# Driver_Low.net
KiCad netlist of a schematic drawn in EAGLE
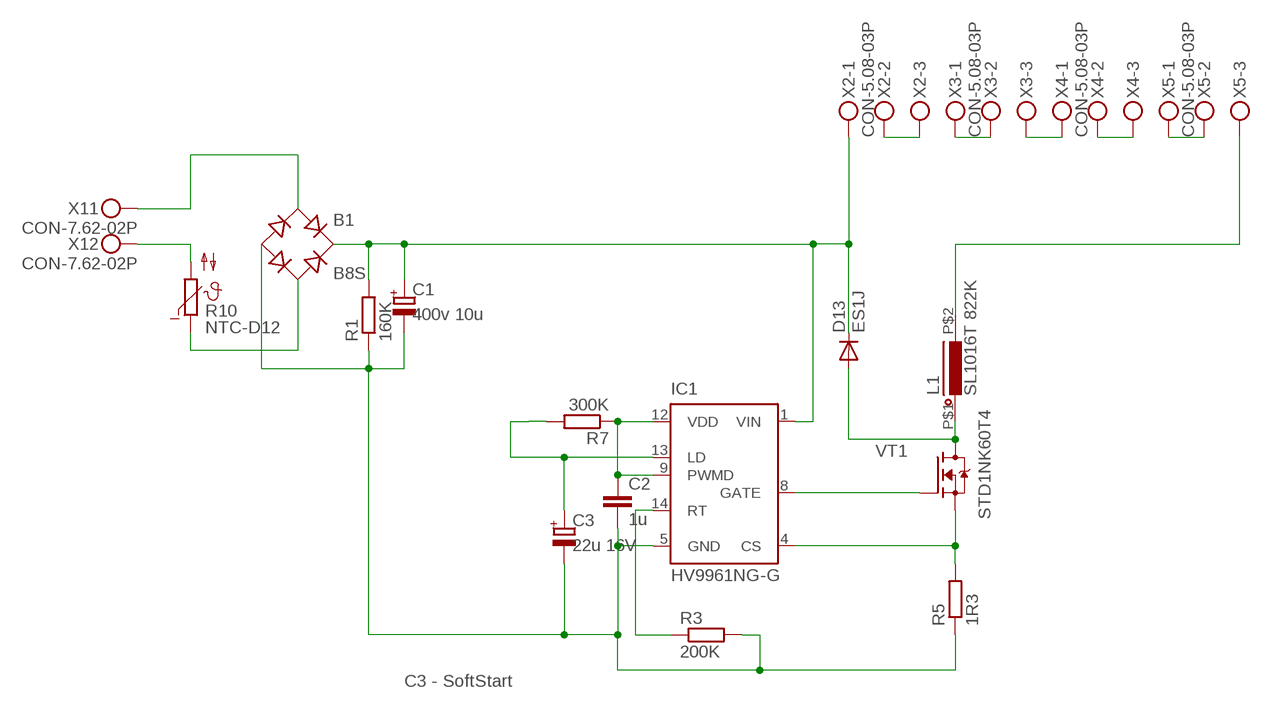
[diagram p0: schematic, sheet 1]
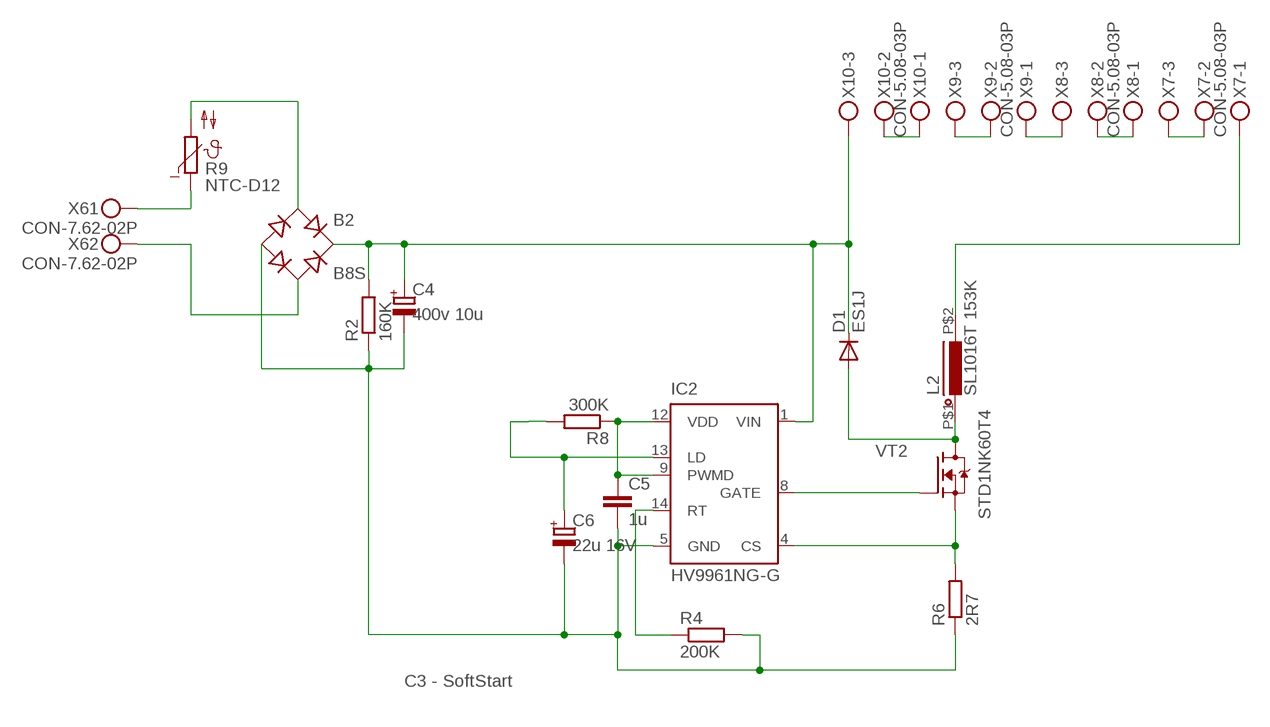
[diagram p1: schematic, sheet 2]

(export (version "E")
  (design (tool "Eeschema 10.0.6"))
  (components
    (comp (ref "B2")
      (value "B8S")
      (footprint "eagle-import:MBS")
      (libsource (lib "eagle-import") (part "BS6"))
    )
    (comp (ref "C4")
      (value "400v 10u")
      (footprint "eagle-import:E3,5-8")
      (libsource (lib "eagle-import") (part "CAP-POL_E3.5-8"))
    )
    (comp (ref "C5")
      (value "1u")
      (footprint "eagle-import:C0805")
      (libsource (lib "eagle-import") (part "CAP_0805"))
    )
    (comp (ref "C6")
      (value "22u 16V")
      (footprint "eagle-import:CT3528")
      (libsource (lib "eagle-import") (part "CAP-POL_3528"))
    )
    (comp (ref "D1")
      (value "ES1J")
      (footprint "eagle-import:DO214AC")
      (libsource (lib "eagle-import") (part "DIODE_ES1J"))
    )
    (comp (ref "IC2")
      (value "HV9961NG-G")
      (footprint "eagle-import:SOIC-16NG")
      (libsource (lib "eagle-import") (part "HV9910BNG"))
    )
    (comp (ref "L2")
      (value "SL1016T 153K")
      (footprint "eagle-import:SL1016")
      (libsource (lib "eagle-import") (part "INDUCTORSL1016"))
    )
    (comp (ref "R2")
      (value "160K")
      (footprint "eagle-import:MF-0125")
      (libsource (lib "eagle-import") (part "R_MF-0125"))
    )
    (comp (ref "R4")
      (value "200K")
      (footprint "eagle-import:R0805")
      (libsource (lib "eagle-import") (part "R_0805"))
    )
    (comp (ref "R6")
      (value "2R7")
      (footprint "eagle-import:R0805")
      (libsource (lib "eagle-import") (part "R_0805"))
    )
    (comp (ref "R8")
      (value "300K")
      (footprint "eagle-import:R0805")
      (libsource (lib "eagle-import") (part "R_0805"))
    )
    (comp (ref "R9")
      (value "NTC-D12")
      (footprint "eagle-import:NTC-D12")
      (libsource (lib "eagle-import") (part "NTC-D12"))
    )
    (comp (ref "VT2")
      (value "STD1NK60T4")
      (footprint "eagle-import:DPAK")
      (libsource (lib "eagle-import") (part "FET-NDPAK"))
    )
    (comp (ref "X6")
      (value "CON-7.62-02P")
      (footprint "eagle-import:KF25C-7.62-02P-13")
      (libsource (lib "eagle-import") (part "CON-7.62-02P"))
    )
    (comp (ref "X7")
      (value "CON-5.08-03P")
      (footprint "eagle-import:MKDSN1,5_3-5,08")
      (libsource (lib "eagle-import") (part "CON-5.08-03P"))
    )
    (comp (ref "X8")
      (value "CON-5.08-03P")
      (footprint "eagle-import:MKDSN1,5_3-5,08")
      (libsource (lib "eagle-import") (part "CON-5.08-03P"))
    )
    (comp (ref "X9")
      (value "CON-5.08-03P")
      (footprint "eagle-import:MKDSN1,5_3-5,08")
      (libsource (lib "eagle-import") (part "CON-5.08-03P"))
    )
    (comp (ref "X10")
      (value "CON-5.08-03P")
      (footprint "eagle-import:MKDSN1,5_3-5,08")
      (libsource (lib "eagle-import") (part "CON-5.08-03P"))
    )
    (comp (ref "B1")
      (value "B8S")
      (footprint "eagle-import:MBS")
      (libsource (lib "eagle-import") (part "BS6"))
    )
    (comp (ref "C1")
      (value "400v 10u")
      (footprint "eagle-import:E3,5-8")
      (libsource (lib "eagle-import") (part "CAP-POL_E3.5-8"))
    )
    (comp (ref "C2")
      (value "1u")
      (footprint "eagle-import:C0805")
      (libsource (lib "eagle-import") (part "CAP_0805"))
    )
    (comp (ref "C3")
      (value "22u 16V")
      (footprint "eagle-import:CT3528")
      (libsource (lib "eagle-import") (part "CAP-POL_3528"))
    )
    (comp (ref "D13")
      (value "ES1J")
      (footprint "eagle-import:DO214AC")
      (libsource (lib "eagle-import") (part "DIODE_ES1J"))
    )
    (comp (ref "IC1")
      (value "HV9961NG-G")
      (footprint "eagle-import:SOIC-16NG")
      (libsource (lib "eagle-import") (part "HV9910BNG"))
    )
    (comp (ref "L1")
      (value "SL1016T 822K")
      (footprint "eagle-import:SL1016")
      (libsource (lib "eagle-import") (part "INDUCTORSL1016"))
    )
    (comp (ref "R1")
      (value "160K")
      (footprint "eagle-import:MF-0125")
      (libsource (lib "eagle-import") (part "R_MF-0125"))
    )
    (comp (ref "R3")
      (value "200K")
      (footprint "eagle-import:R0805")
      (libsource (lib "eagle-import") (part "R_0805"))
    )
    (comp (ref "R5")
      (value "1R3")
      (footprint "eagle-import:R0805")
      (libsource (lib "eagle-import") (part "R_0805"))
    )
    (comp (ref "R7")
      (value "300K")
      (footprint "eagle-import:R0805")
      (libsource (lib "eagle-import") (part "R_0805"))
    )
    (comp (ref "R10")
      (value "NTC-D12")
      (footprint "eagle-import:NTC-D12")
      (libsource (lib "eagle-import") (part "NTC-D12"))
    )
    (comp (ref "VT1")
      (value "STD1NK60T4")
      (footprint "eagle-import:DPAK")
      (libsource (lib "eagle-import") (part "FET-NDPAK"))
    )
    (comp (ref "X1")
      (value "CON-7.62-02P")
      (footprint "eagle-import:KF25C-7.62-02P-13")
      (libsource (lib "eagle-import") (part "CON-7.62-02P"))
    )
    (comp (ref "X2")
      (value "CON-5.08-03P")
      (footprint "eagle-import:MKDSN1,5_3-5,08")
      (libsource (lib "eagle-import") (part "CON-5.08-03P"))
    )
    (comp (ref "X3")
      (value "CON-5.08-03P")
      (footprint "eagle-import:MKDSN1,5_3-5,08")
      (libsource (lib "eagle-import") (part "CON-5.08-03P"))
    )
    (comp (ref "X4")
      (value "CON-5.08-03P")
      (footprint "eagle-import:MKDSN1,5_3-5,08")
      (libsource (lib "eagle-import") (part "CON-5.08-03P"))
    )
    (comp (ref "X5")
      (value "CON-5.08-03P")
      (footprint "eagle-import:MKDSN1,5_3-5,08")
      (libsource (lib "eagle-import") (part "CON-5.08-03P"))
    )
  )
  (nets
    (net (code "1") (name "Net-(B1-PadAC2)") (class "Default")
      (node (ref "B1") (pin "AC2") (pinfunction "AC2_AC2") (pintype "passive"))
      (node (ref "R10") (pin "1") (pinfunction "1_1") (pintype "passive"))
    )
    (net (code "2") (name "Net-(B2-PadAC1)") (class "Default")
      (node (ref "B2") (pin "AC1") (pinfunction "AC1_AC1") (pintype "passive"))
      (node (ref "R9") (pin "2") (pinfunction "2_2") (pintype "passive"))
    )
    (net (code "3") (name "Net-(IC1-CS)") (class "Default")
      (node (ref "IC1") (pin "4") (pinfunction "CS_4") (pintype "input"))
      (node (ref "R5") (pin "2") (pinfunction "2_2") (pintype "passive"))
      (node (ref "VT1") (pin "S") (pinfunction "S_S") (pintype "passive"))
    )
    (net (code "4") (name "Net-(IC1-GATE)") (class "Default")
      (node (ref "IC1") (pin "8") (pinfunction "GATE_8") (pintype "output"))
      (node (ref "VT1") (pin "G") (pinfunction "G_G") (pintype "passive"))
    )
    (net (code "5") (name "Net-(IC1-GND)") (class "Default")
      (node (ref "B1") (pin "-") (pinfunction "-_-") (pintype "passive"))
      (node (ref "C1") (pin "-") (pinfunction "-_-") (pintype "passive"))
      (node (ref "C2") (pin "2") (pinfunction "2_2") (pintype "passive"))
      (node (ref "C3") (pin "-") (pinfunction "-_-") (pintype "passive"))
      (node (ref "IC1") (pin "5") (pinfunction "GND_5") (pintype "power_in"))
      (node (ref "R1") (pin "1") (pinfunction "1_1") (pintype "passive"))
      (node (ref "R3") (pin "2") (pinfunction "2_2") (pintype "passive"))
      (node (ref "R5") (pin "1") (pinfunction "1_1") (pintype "passive"))
    )
    (net (code "6") (name "Net-(IC1-LD)") (class "Default")
      (node (ref "C3") (pin "+") (pinfunction "+_+") (pintype "passive"))
      (node (ref "IC1") (pin "13") (pinfunction "LD_13") (pintype "input"))
      (node (ref "R7") (pin "2") (pinfunction "2_2") (pintype "passive"))
    )
    (net (code "7") (name "Net-(IC1-PWMD)") (class "Default")
      (node (ref "C2") (pin "1") (pinfunction "1_1") (pintype "passive"))
      (node (ref "IC1") (pin "12") (pinfunction "VDD_12") (pintype "power_in"))
      (node (ref "IC1") (pin "9") (pinfunction "PWMD_9") (pintype "input"))
      (node (ref "R7") (pin "1") (pinfunction "1_1") (pintype "passive"))
    )
    (net (code "8") (name "Net-(IC1-RT)") (class "Default")
      (node (ref "IC1") (pin "14") (pinfunction "RT_14") (pintype "passive"))
      (node (ref "R3") (pin "1") (pinfunction "1_1") (pintype "passive"))
    )
    (net (code "9") (name "Net-(IC1-VIN)") (class "Default")
      (node (ref "B1") (pin "+") (pinfunction "+_+") (pintype "passive"))
      (node (ref "C1") (pin "+") (pinfunction "+_+") (pintype "passive"))
      (node (ref "D13") (pin "C") (pinfunction "C_C") (pintype "passive"))
      (node (ref "IC1") (pin "1") (pinfunction "VIN_1") (pintype "input"))
      (node (ref "R1") (pin "2") (pinfunction "2_2") (pintype "passive"))
      (node (ref "X2") (pin "1") (pinfunction "KL_1") (pintype "passive"))
    )
    (net (code "10") (name "Net-(IC2-CS)") (class "Default")
      (node (ref "IC2") (pin "4") (pinfunction "CS_4") (pintype "input"))
      (node (ref "R6") (pin "2") (pinfunction "2_2") (pintype "passive"))
      (node (ref "VT2") (pin "S") (pinfunction "S_S") (pintype "passive"))
    )
    (net (code "11") (name "Net-(IC2-GATE)") (class "Default")
      (node (ref "IC2") (pin "8") (pinfunction "GATE_8") (pintype "output"))
      (node (ref "VT2") (pin "G") (pinfunction "G_G") (pintype "passive"))
    )
    (net (code "12") (name "Net-(IC2-GND)") (class "Default")
      (node (ref "B2") (pin "-") (pinfunction "-_-") (pintype "passive"))
      (node (ref "C4") (pin "-") (pinfunction "-_-") (pintype "passive"))
      (node (ref "C5") (pin "2") (pinfunction "2_2") (pintype "passive"))
      (node (ref "C6") (pin "-") (pinfunction "-_-") (pintype "passive"))
      (node (ref "IC2") (pin "5") (pinfunction "GND_5") (pintype "power_in"))
      (node (ref "R2") (pin "1") (pinfunction "1_1") (pintype "passive"))
      (node (ref "R4") (pin "2") (pinfunction "2_2") (pintype "passive"))
      (node (ref "R6") (pin "1") (pinfunction "1_1") (pintype "passive"))
    )
    (net (code "13") (name "Net-(IC2-LD)") (class "Default")
      (node (ref "C6") (pin "+") (pinfunction "+_+") (pintype "passive"))
      (node (ref "IC2") (pin "13") (pinfunction "LD_13") (pintype "input"))
      (node (ref "R8") (pin "2") (pinfunction "2_2") (pintype "passive"))
    )
    (net (code "14") (name "Net-(IC2-PWMD)") (class "Default")
      (node (ref "C5") (pin "1") (pinfunction "1_1") (pintype "passive"))
      (node (ref "IC2") (pin "12") (pinfunction "VDD_12") (pintype "power_in"))
      (node (ref "IC2") (pin "9") (pinfunction "PWMD_9") (pintype "input"))
      (node (ref "R8") (pin "1") (pinfunction "1_1") (pintype "passive"))
    )
    (net (code "15") (name "Net-(IC2-RT)") (class "Default")
      (node (ref "IC2") (pin "14") (pinfunction "RT_14") (pintype "passive"))
      (node (ref "R4") (pin "1") (pinfunction "1_1") (pintype "passive"))
    )
    (net (code "16") (name "Net-(IC2-VIN)") (class "Default")
      (node (ref "B2") (pin "+") (pinfunction "+_+") (pintype "passive"))
      (node (ref "C4") (pin "+") (pinfunction "+_+") (pintype "passive"))
      (node (ref "D1") (pin "C") (pinfunction "C_C") (pintype "passive"))
      (node (ref "IC2") (pin "1") (pinfunction "VIN_1") (pintype "input"))
      (node (ref "R2") (pin "2") (pinfunction "2_2") (pintype "passive"))
      (node (ref "X10") (pin "3") (pinfunction "KL_3") (pintype "passive"))
    )
    (net (code "17") (name "Net-(L1-1)") (class "Default")
      (node (ref "D13") (pin "A") (pinfunction "A_A") (pintype "passive"))
      (node (ref "L1") (pin "P$1") (pinfunction "1_P$1") (pintype "passive"))
      (node (ref "VT1") (pin "D") (pinfunction "D_D") (pintype "passive"))
    )
    (net (code "18") (name "Net-(L1-2)") (class "Default")
      (node (ref "L1") (pin "P$2") (pinfunction "2_P$2") (pintype "passive"))
      (node (ref "X5") (pin "3") (pinfunction "KL_3") (pintype "passive"))
    )
    (net (code "19") (name "Net-(L2-1)") (class "Default")
      (node (ref "D1") (pin "A") (pinfunction "A_A") (pintype "passive"))
      (node (ref "L2") (pin "P$1") (pinfunction "1_P$1") (pintype "passive"))
      (node (ref "VT2") (pin "D") (pinfunction "D_D") (pintype "passive"))
    )
    (net (code "20") (name "Net-(L2-2)") (class "Default")
      (node (ref "L2") (pin "P$2") (pinfunction "2_P$2") (pintype "passive"))
      (node (ref "X7") (pin "1") (pinfunction "KL_1") (pintype "passive"))
    )
    (net (code "21") (name "Net-(X1A-KL)") (class "Default")
      (node (ref "B1") (pin "AC1") (pinfunction "AC1_AC1") (pintype "passive"))
      (node (ref "X1") (pin "P$1") (pinfunction "KL_P$1") (pintype "passive"))
    )
    (net (code "22") (name "Net-(X1B-KL)") (class "Default")
      (node (ref "R10") (pin "2") (pinfunction "2_2") (pintype "passive"))
      (node (ref "X1") (pin "P$2") (pinfunction "KL_P$2") (pintype "passive"))
    )
    (net (code "23") (name "Net-(X2B-KL)") (class "Default")
      (node (ref "X2") (pin "2") (pinfunction "KL_2") (pintype "passive"))
      (node (ref "X2") (pin "3") (pinfunction "KL_3") (pintype "passive"))
    )
    (net (code "24") (name "Net-(X3A-KL)") (class "Default")
      (node (ref "X3") (pin "1") (pinfunction "KL_1") (pintype "passive"))
      (node (ref "X3") (pin "2") (pinfunction "KL_2") (pintype "passive"))
    )
    (net (code "25") (name "Net-(X3C-KL)") (class "Default")
      (node (ref "X3") (pin "3") (pinfunction "KL_3") (pintype "passive"))
      (node (ref "X4") (pin "1") (pinfunction "KL_1") (pintype "passive"))
    )
    (net (code "26") (name "Net-(X4B-KL)") (class "Default")
      (node (ref "X4") (pin "2") (pinfunction "KL_2") (pintype "passive"))
      (node (ref "X4") (pin "3") (pinfunction "KL_3") (pintype "passive"))
    )
    (net (code "27") (name "Net-(X5A-KL)") (class "Default")
      (node (ref "X5") (pin "1") (pinfunction "KL_1") (pintype "passive"))
      (node (ref "X5") (pin "2") (pinfunction "KL_2") (pintype "passive"))
    )
    (net (code "28") (name "Net-(X6A-KL)") (class "Default")
      (node (ref "R9") (pin "1") (pinfunction "1_1") (pintype "passive"))
      (node (ref "X6") (pin "P$1") (pinfunction "KL_P$1") (pintype "passive"))
    )
    (net (code "29") (name "Net-(X6B-KL)") (class "Default")
      (node (ref "B2") (pin "AC2") (pinfunction "AC2_AC2") (pintype "passive"))
      (node (ref "X6") (pin "P$2") (pinfunction "KL_P$2") (pintype "passive"))
    )
    (net (code "30") (name "Net-(X7B-KL)") (class "Default")
      (node (ref "X7") (pin "2") (pinfunction "KL_2") (pintype "passive"))
      (node (ref "X7") (pin "3") (pinfunction "KL_3") (pintype "passive"))
    )
    (net (code "31") (name "Net-(X8A-KL)") (class "Default")
      (node (ref "X8") (pin "1") (pinfunction "KL_1") (pintype "passive"))
      (node (ref "X8") (pin "2") (pinfunction "KL_2") (pintype "passive"))
    )
    (net (code "32") (name "Net-(X8C-KL)") (class "Default")
      (node (ref "X8") (pin "3") (pinfunction "KL_3") (pintype "passive"))
      (node (ref "X9") (pin "1") (pinfunction "KL_1") (pintype "passive"))
    )
    (net (code "33") (name "Net-(X9B-KL)") (class "Default")
      (node (ref "X9") (pin "2") (pinfunction "KL_2") (pintype "passive"))
      (node (ref "X9") (pin "3") (pinfunction "KL_3") (pintype "passive"))
    )
    (net (code "34") (name "Net-(X10A-KL)") (class "Default")
      (node (ref "X10") (pin "1") (pinfunction "KL_1") (pintype "passive"))
      (node (ref "X10") (pin "2") (pinfunction "KL_2") (pintype "passive"))
    )
  )
)
